# Moinak_BLDC.net
KiCad netlist of a schematic drawn in EAGLE
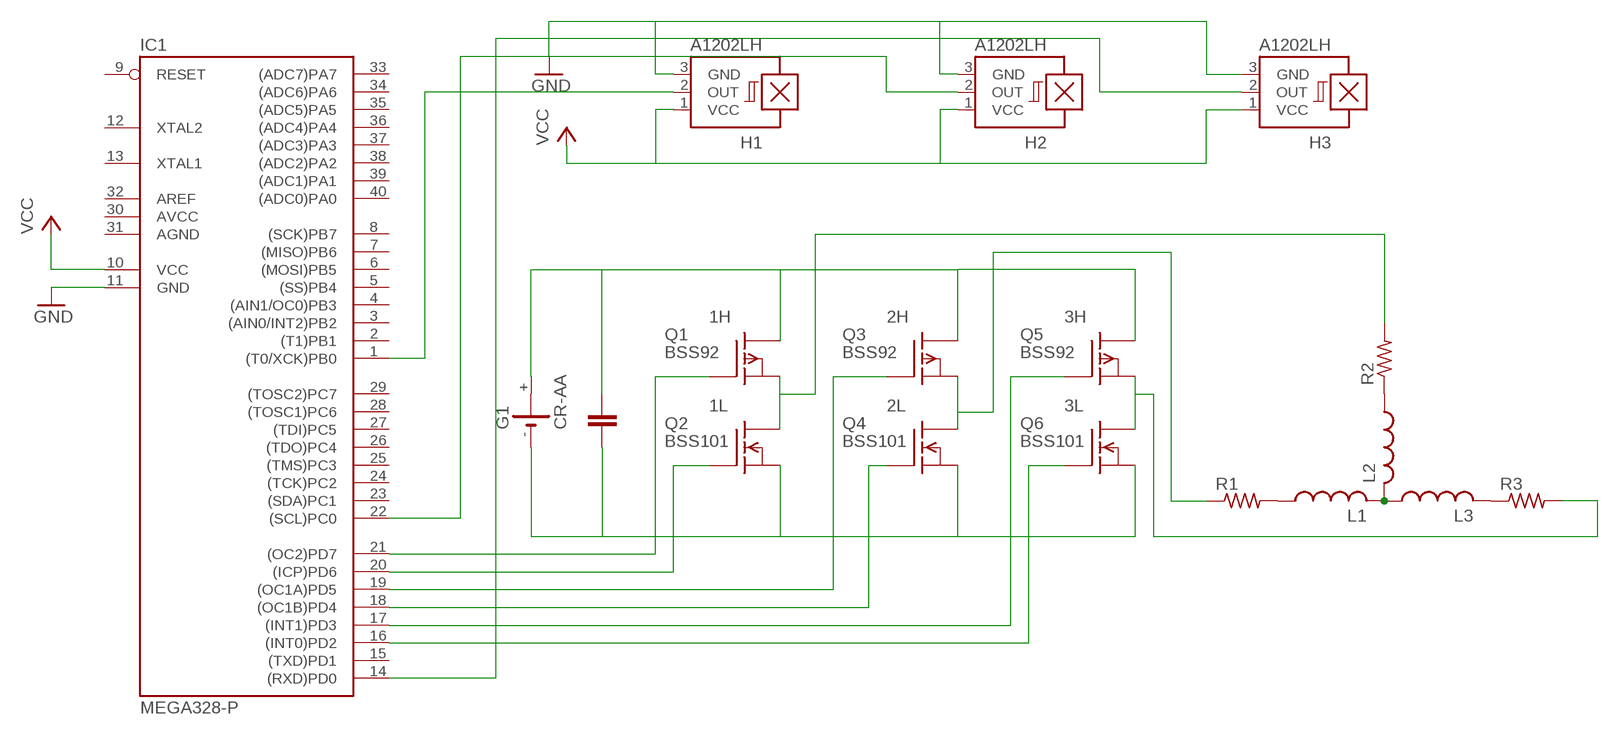
[diagram p0: schematic, sheet 1]

(export (version "E")
  (design (tool "Eeschema 10.0.6"))
  (components
    (comp (ref "G1")
      (value "CR-AA")
      (footprint "eagle-import:CRAA")
      (libsource (lib "eagle-import") (part "CR-AA"))
    )
    (comp (ref "H1")
      (value "A1202LH")
      (footprint "eagle-import:SOT23-W")
      (libsource (lib "eagle-import") (part "A12?LH02"))
    )
    (comp (ref "H2")
      (value "A1202LH")
      (footprint "eagle-import:SOT23-W")
      (libsource (lib "eagle-import") (part "A12?LH02"))
    )
    (comp (ref "H3")
      (value "A1202LH")
      (footprint "eagle-import:SOT23-W")
      (libsource (lib "eagle-import") (part "A12?LH02"))
    )
    (comp (ref "IC1")
      (value "MEGA328-P")
      (footprint "eagle-import:DIL40")
      (libsource (lib "eagle-import") (part "MEGA323-P"))
    )
    (comp (ref "L1")
      (value "L-USIR-2")
      (footprint "eagle-import:IR-2")
      (libsource (lib "eagle-import") (part "L-USIR-2"))
    )
    (comp (ref "L2")
      (value "L-USIR-2")
      (footprint "eagle-import:IR-2")
      (libsource (lib "eagle-import") (part "L-USIR-2"))
    )
    (comp (ref "L3")
      (value "L-USIR-2")
      (footprint "eagle-import:IR-2")
      (libsource (lib "eagle-import") (part "L-USIR-2"))
    )
    (comp (ref "Q1")
      (value "BSS92")
      (footprint "eagle-import:TO92")
      (libsource (lib "eagle-import") (part "BSS92"))
    )
    (comp (ref "Q2")
      (value "BSS101")
      (footprint "eagle-import:TO92")
      (libsource (lib "eagle-import") (part "BSS101"))
    )
    (comp (ref "Q3")
      (value "BSS92")
      (footprint "eagle-import:TO92")
      (libsource (lib "eagle-import") (part "BSS92"))
    )
    (comp (ref "Q4")
      (value "BSS101")
      (footprint "eagle-import:TO92")
      (libsource (lib "eagle-import") (part "BSS101"))
    )
    (comp (ref "Q5")
      (value "BSS92")
      (footprint "eagle-import:TO92")
      (libsource (lib "eagle-import") (part "BSS92"))
    )
    (comp (ref "Q6")
      (value "BSS101")
      (footprint "eagle-import:TO92")
      (libsource (lib "eagle-import") (part "BSS101"))
    )
    (comp (ref "R1")
      (value "R-US_0309/12")
      (footprint "eagle-import:0309_12")
      (libsource (lib "eagle-import") (part "R-US_0309/12"))
    )
    (comp (ref "R2")
      (value "R-US_0309/12")
      (footprint "eagle-import:0309_12")
      (libsource (lib "eagle-import") (part "R-US_0309/12"))
    )
    (comp (ref "R3")
      (value "R-US_0309/12")
      (footprint "eagle-import:0309_12")
      (libsource (lib "eagle-import") (part "R-US_0309/12"))
    )
  )
  (nets
    (net (code "1") (name "/1H") (class "Default")
      (node (ref "IC1") (pin "21") (pinfunction "(OC2)PD7_21") (pintype "bidirectional"))
      (node (ref "Q1") (pin "1") (pinfunction "G_1") (pintype "passive"))
    )
    (net (code "2") (name "/1L") (class "Default")
      (node (ref "G1") (pin "-") (pinfunction "-_-") (pintype "passive"))
      (node (ref "IC1") (pin "20") (pinfunction "(ICP)PD6_20") (pintype "bidirectional"))
      (node (ref "Q2") (pin "1") (pinfunction "S_1") (pintype "passive"))
      (node (ref "Q2") (pin "2") (pinfunction "G_2") (pintype "passive"))
      (node (ref "Q4") (pin "1") (pinfunction "S_1") (pintype "passive"))
      (node (ref "Q6") (pin "1") (pinfunction "S_1") (pintype "passive"))
    )
    (net (code "3") (name "/2H") (class "Default")
      (node (ref "IC1") (pin "19") (pinfunction "(OC1A)PD5_19") (pintype "bidirectional"))
      (node (ref "Q3") (pin "1") (pinfunction "G_1") (pintype "passive"))
    )
    (net (code "4") (name "/2L") (class "Default")
      (node (ref "IC1") (pin "18") (pinfunction "(OC1B)PD4_18") (pintype "bidirectional"))
      (node (ref "Q4") (pin "2") (pinfunction "G_2") (pintype "passive"))
    )
    (net (code "5") (name "/3H") (class "Default")
      (node (ref "IC1") (pin "17") (pinfunction "(INT1)PD3_17") (pintype "bidirectional"))
      (node (ref "Q5") (pin "1") (pinfunction "G_1") (pintype "passive"))
    )
    (net (code "6") (name "/3L") (class "Default")
      (node (ref "IC1") (pin "16") (pinfunction "(INT0)PD2_16") (pintype "bidirectional"))
      (node (ref "Q6") (pin "2") (pinfunction "G_2") (pintype "passive"))
    )
    (net (code "7") (name "/AGND") (class "Default")
      (node (ref "IC1") (pin "31") (pinfunction "AGND_31") (pintype "power_in"))
    )
    (net (code "8") (name "/AVCC") (class "Default")
      (node (ref "IC1") (pin "30") (pinfunction "AVCC_30") (pintype "power_in"))
    )
    (net (code "9") (name "GND") (class "Default")
      (node (ref "H1") (pin "3") (pinfunction "GND_3") (pintype "power_in"))
      (node (ref "H2") (pin "3") (pinfunction "GND_3") (pintype "power_in"))
      (node (ref "H3") (pin "3") (pinfunction "GND_3") (pintype "power_in"))
      (node (ref "IC1") (pin "11") (pinfunction "GND_11") (pintype "power_in"))
    )
    (net (code "10") (name "Net-(H1-OUT)") (class "Default")
      (node (ref "H1") (pin "2") (pinfunction "OUT_2") (pintype "output"))
      (node (ref "IC1") (pin "1") (pinfunction "(T0/XCK)PB0_1") (pintype "bidirectional"))
    )
    (net (code "11") (name "Net-(H2-OUT)") (class "Default")
      (node (ref "H2") (pin "2") (pinfunction "OUT_2") (pintype "output"))
      (node (ref "IC1") (pin "22") (pinfunction "(SCL)PC0_22") (pintype "bidirectional"))
    )
    (net (code "12") (name "Net-(H3-OUT)") (class "Default")
      (node (ref "H3") (pin "2") (pinfunction "OUT_2") (pintype "output"))
      (node (ref "IC1") (pin "14") (pinfunction "(RXD)PD0_14") (pintype "bidirectional"))
    )
    (net (code "13") (name "Net-(L1-Pad1)") (class "Default")
      (node (ref "L1") (pin "1") (pinfunction "1_1") (pintype "passive"))
      (node (ref "R1") (pin "2") (pinfunction "2_2") (pintype "passive"))
    )
    (net (code "14") (name "Net-(L1-Pad2)") (class "Default")
      (node (ref "L1") (pin "2") (pinfunction "2_2") (pintype "passive"))
      (node (ref "L2") (pin "2") (pinfunction "2_2") (pintype "passive"))
      (node (ref "L3") (pin "1") (pinfunction "1_1") (pintype "passive"))
    )
    (net (code "15") (name "Net-(L2-Pad1)") (class "Default")
      (node (ref "L2") (pin "1") (pinfunction "1_1") (pintype "passive"))
      (node (ref "R2") (pin "1") (pinfunction "1_1") (pintype "passive"))
    )
    (net (code "16") (name "Net-(L3-Pad2)") (class "Default")
      (node (ref "L3") (pin "2") (pinfunction "2_2") (pintype "passive"))
      (node (ref "R3") (pin "1") (pinfunction "1_1") (pintype "passive"))
    )
    (net (code "17") (name "Net-(Q1-D)") (class "Default")
      (node (ref "G1") (pin "+") (pinfunction "+_+") (pintype "passive"))
      (node (ref "Q1") (pin "2") (pinfunction "D_2") (pintype "passive"))
      (node (ref "Q3") (pin "2") (pinfunction "D_2") (pintype "passive"))
      (node (ref "Q5") (pin "2") (pinfunction "D_2") (pintype "passive"))
    )
    (net (code "18") (name "Net-(Q1-S)") (class "Default")
      (node (ref "Q1") (pin "3") (pinfunction "S_3") (pintype "passive"))
      (node (ref "Q2") (pin "3") (pinfunction "D_3") (pintype "passive"))
      (node (ref "R2") (pin "2") (pinfunction "2_2") (pintype "passive"))
    )
    (net (code "19") (name "Net-(Q3-S)") (class "Default")
      (node (ref "Q3") (pin "3") (pinfunction "S_3") (pintype "passive"))
      (node (ref "Q4") (pin "3") (pinfunction "D_3") (pintype "passive"))
      (node (ref "R1") (pin "1") (pinfunction "1_1") (pintype "passive"))
    )
    (net (code "20") (name "Net-(Q5-S)") (class "Default")
      (node (ref "Q5") (pin "3") (pinfunction "S_3") (pintype "passive"))
      (node (ref "Q6") (pin "3") (pinfunction "D_3") (pintype "passive"))
      (node (ref "R3") (pin "2") (pinfunction "2_2") (pintype "passive"))
    )
    (net (code "21") (name "VCC") (class "Default")
      (node (ref "H1") (pin "1") (pinfunction "VCC_1") (pintype "power_in"))
      (node (ref "H2") (pin "1") (pinfunction "VCC_1") (pintype "power_in"))
      (node (ref "H3") (pin "1") (pinfunction "VCC_1") (pintype "power_in"))
      (node (ref "IC1") (pin "10") (pinfunction "VCC_10") (pintype "power_in"))
    )
    (net (code "22") (name "unconnected-(G1-+-Pad+@1)") (class "Default")
      (node (ref "G1") (pin "+@1") (pinfunction "+_+@1") (pintype "passive"))
    )
    (net (code "23") (name "unconnected-(IC1-(ADC0)PA0-Pad40)") (class "Default")
      (node (ref "IC1") (pin "40") (pinfunction "(ADC0)PA0_40") (pintype "bidirectional"))
    )
    (net (code "24") (name "unconnected-(IC1-(ADC1)PA1-Pad39)") (class "Default")
      (node (ref "IC1") (pin "39") (pinfunction "(ADC1)PA1_39") (pintype "bidirectional"))
    )
    (net (code "25") (name "unconnected-(IC1-(ADC2)PA2-Pad38)") (class "Default")
      (node (ref "IC1") (pin "38") (pinfunction "(ADC2)PA2_38") (pintype "bidirectional"))
    )
    (net (code "26") (name "unconnected-(IC1-(ADC3)PA3-Pad37)") (class "Default")
      (node (ref "IC1") (pin "37") (pinfunction "(ADC3)PA3_37") (pintype "bidirectional"))
    )
    (net (code "27") (name "unconnected-(IC1-(ADC4)PA4-Pad36)") (class "Default")
      (node (ref "IC1") (pin "36") (pinfunction "(ADC4)PA4_36") (pintype "bidirectional"))
    )
    (net (code "28") (name "unconnected-(IC1-(ADC5)PA5-Pad35)") (class "Default")
      (node (ref "IC1") (pin "35") (pinfunction "(ADC5)PA5_35") (pintype "bidirectional"))
    )
    (net (code "29") (name "unconnected-(IC1-(ADC6)PA6-Pad34)") (class "Default")
      (node (ref "IC1") (pin "34") (pinfunction "(ADC6)PA6_34") (pintype "bidirectional"))
    )
    (net (code "30") (name "unconnected-(IC1-(ADC7)PA7-Pad33)") (class "Default")
      (node (ref "IC1") (pin "33") (pinfunction "(ADC7)PA7_33") (pintype "bidirectional"))
    )
    (net (code "31") (name "unconnected-(IC1-(AIN0{slash}INT2)PB2-Pad3)") (class "Default")
      (node (ref "IC1") (pin "3") (pinfunction "(AIN0/INT2)PB2_3") (pintype "bidirectional"))
    )
    (net (code "32") (name "unconnected-(IC1-(AIN1{slash}OC0)PB3-Pad4)") (class "Default")
      (node (ref "IC1") (pin "4") (pinfunction "(AIN1/OC0)PB3_4") (pintype "bidirectional"))
    )
    (net (code "33") (name "unconnected-(IC1-(MISO)PB6-Pad7)") (class "Default")
      (node (ref "IC1") (pin "7") (pinfunction "(MISO)PB6_7") (pintype "bidirectional"))
    )
    (net (code "34") (name "unconnected-(IC1-(MOSI)PB5-Pad6)") (class "Default")
      (node (ref "IC1") (pin "6") (pinfunction "(MOSI)PB5_6") (pintype "bidirectional"))
    )
    (net (code "35") (name "unconnected-(IC1-(SCK)PB7-Pad8)") (class "Default")
      (node (ref "IC1") (pin "8") (pinfunction "(SCK)PB7_8") (pintype "bidirectional"))
    )
    (net (code "36") (name "unconnected-(IC1-(SDA)PC1-Pad23)") (class "Default")
      (node (ref "IC1") (pin "23") (pinfunction "(SDA)PC1_23") (pintype "bidirectional"))
    )
    (net (code "37") (name "unconnected-(IC1-(SS)PB4-Pad5)") (class "Default")
      (node (ref "IC1") (pin "5") (pinfunction "(SS)PB4_5") (pintype "bidirectional"))
    )
    (net (code "38") (name "unconnected-(IC1-(T1)PB1-Pad2)") (class "Default")
      (node (ref "IC1") (pin "2") (pinfunction "(T1)PB1_2") (pintype "bidirectional"))
    )
    (net (code "39") (name "unconnected-(IC1-(TCK)PC2-Pad24)") (class "Default")
      (node (ref "IC1") (pin "24") (pinfunction "(TCK)PC2_24") (pintype "bidirectional"))
    )
    (net (code "40") (name "unconnected-(IC1-(TDI)PC5-Pad27)") (class "Default")
      (node (ref "IC1") (pin "27") (pinfunction "(TDI)PC5_27") (pintype "bidirectional"))
    )
    (net (code "41") (name "unconnected-(IC1-(TDO)PC4-Pad26)") (class "Default")
      (node (ref "IC1") (pin "26") (pinfunction "(TDO)PC4_26") (pintype "bidirectional"))
    )
    (net (code "42") (name "unconnected-(IC1-(TMS)PC3-Pad25)") (class "Default")
      (node (ref "IC1") (pin "25") (pinfunction "(TMS)PC3_25") (pintype "bidirectional"))
    )
    (net (code "43") (name "unconnected-(IC1-(TOSC1)PC6-Pad28)") (class "Default")
      (node (ref "IC1") (pin "28") (pinfunction "(TOSC1)PC6_28") (pintype "bidirectional"))
    )
    (net (code "44") (name "unconnected-(IC1-(TOSC2)PC7-Pad29)") (class "Default")
      (node (ref "IC1") (pin "29") (pinfunction "(TOSC2)PC7_29") (pintype "bidirectional"))
    )
    (net (code "45") (name "unconnected-(IC1-(TXD)PD1-Pad15)") (class "Default")
      (node (ref "IC1") (pin "15") (pinfunction "(TXD)PD1_15") (pintype "bidirectional"))
    )
    (net (code "46") (name "unconnected-(IC1-AREF-Pad32)") (class "Default")
      (node (ref "IC1") (pin "32") (pinfunction "AREF_32") (pintype "passive"))
    )
    (net (code "47") (name "unconnected-(IC1-RESET-Pad9)") (class "Default")
      (node (ref "IC1") (pin "9") (pinfunction "RESET_9") (pintype "input"))
    )
    (net (code "48") (name "unconnected-(IC1-XTAL1-Pad13)") (class "Default")
      (node (ref "IC1") (pin "13") (pinfunction "XTAL1_13") (pintype "bidirectional"))
    )
    (net (code "49") (name "unconnected-(IC1-XTAL2-Pad12)") (class "Default")
      (node (ref "IC1") (pin "12") (pinfunction "XTAL2_12") (pintype "bidirectional"))
    )
  )
)
